# UI.net
KiCad netlist of a schematic drawn in Altium Designer
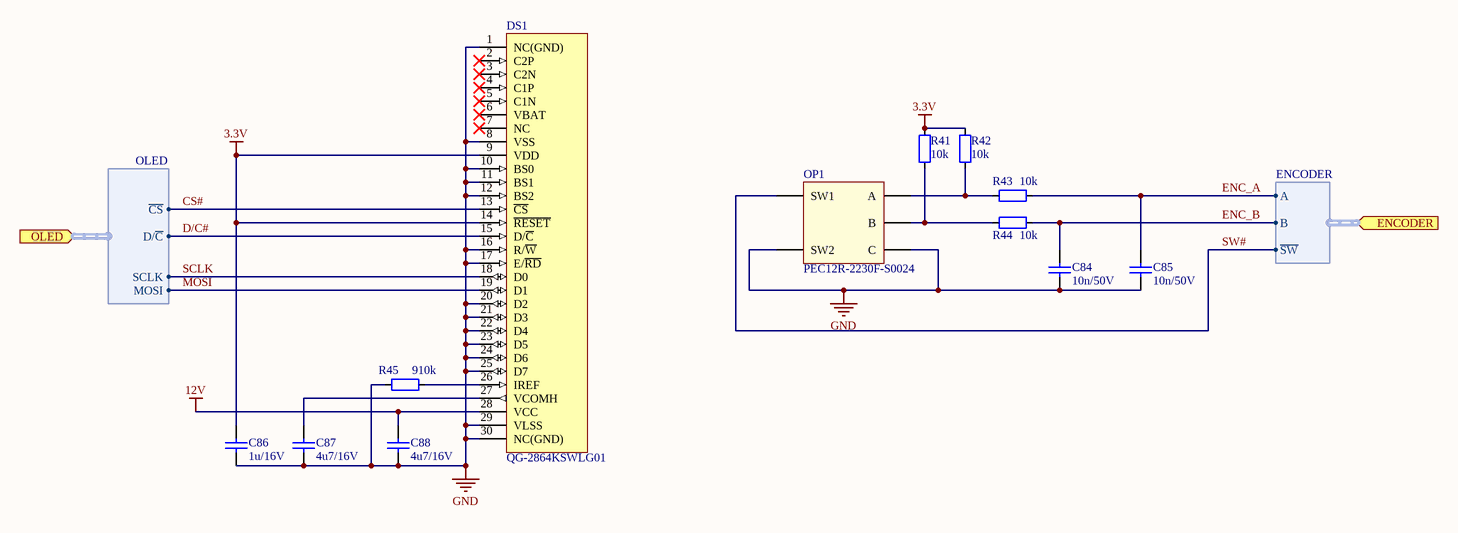
[diagram p0: UI.SchDoc]

(export (version "E")
  (design (tool "Eeschema 10.0.6"))
  (components
    (comp (ref "C84")
      (value "10n/50V")
      (footprint "C0402")
      (fields (field (name "VOLTAGE") "50V") (field (name "TOLERANCE") "10%"))
      (libsource (lib "dk_capacitors") (part "10n 50V X7R 0402"))
    )
    (comp (ref "C85")
      (value "10n/50V")
      (footprint "C0402")
      (fields (field (name "VOLTAGE") "50V") (field (name "TOLERANCE") "10%"))
      (libsource (lib "dk_capacitors") (part "10n 50V X7R 0402"))
    )
    (comp (ref "C86")
      (value "1u/16V")
      (footprint "C0603")
      (fields (field (name "VOLTAGE") "16V") (field (name "TOLERANCE") "10%"))
      (libsource (lib "dk_capacitors") (part "1u 16V X7R 0603"))
    )
    (comp (ref "C87")
      (value "4u7/16V")
      (footprint "C0805")
      (fields (field (name "VOLTAGE") "16V") (field (name "TOLERANCE") "10%"))
      (libsource (lib "dk_capacitors") (part "4u7 16V X7R 0805"))
    )
    (comp (ref "C88")
      (value "4u7/16V")
      (footprint "C0805")
      (fields (field (name "VOLTAGE") "16V") (field (name "TOLERANCE") "10%"))
      (libsource (lib "dk_capacitors") (part "4u7 16V X7R 0805"))
    )
    (comp (ref "DS1")
      (value "QG-2864KSWLG01")
      (footprint "QG-2864KSWLG01")
      (description "OLED, 1.3-inch, 128x64, SPI")
      (libsource (lib "dk_optoelectronics") (part "QG-2864KSWLG01"))
    )
    (comp (ref "OP1")
      (value "PEC12R-2230F-S0024")
      (footprint "PEC12R-2x30F-Sxxxx")
      (description "Rotary Encoder Mechanical 24 Quadrature (Incremental) Right Angle")
      (libsource (lib "dk_electromechanical") (part "PEC12R-2230F-S0024"))
    )
    (comp (ref "R41")
      (value "10k")
      (footprint "R0402")
      (fields (field (name "TOLERANCE") "1%") (field (name "VOLTAGE") "50V"))
      (libsource (lib "") (part "10k 63mW 50V 0402_1"))
    )
    (comp (ref "R42")
      (value "10k")
      (footprint "R0402")
      (fields (field (name "TOLERANCE") "1%") (field (name "VOLTAGE") "50V"))
      (libsource (lib "") (part "10k 63mW 50V 0402_1"))
    )
    (comp (ref "R43")
      (value "10k")
      (footprint "R0402")
      (fields (field (name "TOLERANCE") "1%") (field (name "VOLTAGE") "50V"))
      (libsource (lib "dk_resistors") (part "10k 63mW 50V 0402"))
    )
    (comp (ref "R44")
      (value "10k")
      (footprint "R0402")
      (fields (field (name "TOLERANCE") "1%") (field (name "VOLTAGE") "50V"))
      (libsource (lib "dk_resistors") (part "10k 63mW 50V 0402"))
    )
    (comp (ref "R45")
      (value "910k")
      (footprint "R0402")
      (fields (field (name "TOLERANCE") "5%") (field (name "VOLTAGE") "50V"))
      (libsource (lib "dk_resistors") (part "910k 63mW 50V 0402"))
    )
  )
  (nets
    (net (code "3") (name "/CS#") (class "Default")
      (node (ref "DS1") (pin "13") (pinfunction "~{CS}_13") (pintype "input"))
    )
    (net (code "4") (name "/D{slash}C#") (class "Default")
      (node (ref "DS1") (pin "15") (pinfunction "D/~{C}_15") (pintype "input"))
    )
    (net (code "5") (name "/ENC_A") (class "Default")
      (node (ref "C85") (pin "2") (pinfunction "2_2") (pintype "passive"))
      (node (ref "R43") (pin "2") (pinfunction "2_2") (pintype "passive"))
    )
    (net (code "6") (name "/ENC_B") (class "Default")
      (node (ref "C84") (pin "2") (pinfunction "2_2") (pintype "passive"))
      (node (ref "R44") (pin "2") (pinfunction "2_2") (pintype "passive"))
    )
    (net (code "7") (name "/MOSI") (class "Default")
      (node (ref "DS1") (pin "19") (pinfunction "D1_19") (pintype "bidirectional"))
    )
    (net (code "8") (name "/SCLK") (class "Default")
      (node (ref "DS1") (pin "18") (pinfunction "D0_18") (pintype "bidirectional"))
    )
    (net (code "9") (name "/SW#") (class "Default")
      (node (ref "OP1") (pin "1") (pinfunction "SW1_1") (pintype "passive"))
    )
    (net (code "12") (name "3.3V") (class "Default")
      (node (ref "C86") (pin "2") (pinfunction "2_2") (pintype "passive"))
      (node (ref "DS1") (pin "14") (pinfunction "~{RESET}_14") (pintype "input"))
      (node (ref "DS1") (pin "9") (pinfunction "VDD_9") (pintype "power_in"))
      (node (ref "R41") (pin "2") (pinfunction "2_2") (pintype "passive"))
      (node (ref "R42") (pin "2") (pinfunction "2_2") (pintype "passive"))
    )
    (net (code "13") (name "12V") (class "Default")
      (node (ref "C88") (pin "2") (pinfunction "2_2") (pintype "passive"))
      (node (ref "DS1") (pin "28") (pinfunction "VCC_28") (pintype "power_in"))
    )
    (net (code "14") (name "GND") (class "Default")
      (node (ref "C84") (pin "1") (pinfunction "1_1") (pintype "passive"))
      (node (ref "C85") (pin "1") (pinfunction "1_1") (pintype "passive"))
      (node (ref "C86") (pin "1") (pinfunction "1_1") (pintype "passive"))
      (node (ref "C87") (pin "1") (pinfunction "1_1") (pintype "passive"))
      (node (ref "C88") (pin "1") (pinfunction "1_1") (pintype "passive"))
      (node (ref "DS1") (pin "1") (pinfunction "NC(GND)_1") (pintype "passive"))
      (node (ref "DS1") (pin "10") (pinfunction "BS0_10") (pintype "input"))
      (node (ref "DS1") (pin "11") (pinfunction "BS1_11") (pintype "input"))
      (node (ref "DS1") (pin "12") (pinfunction "BS2_12") (pintype "input"))
      (node (ref "DS1") (pin "16") (pinfunction "R/~{W}_16") (pintype "input"))
      (node (ref "DS1") (pin "17") (pinfunction "E/~{RD}_17") (pintype "input"))
      (node (ref "DS1") (pin "20") (pinfunction "D2_20") (pintype "bidirectional"))
      (node (ref "DS1") (pin "21") (pinfunction "D3_21") (pintype "bidirectional"))
      (node (ref "DS1") (pin "22") (pinfunction "D4_22") (pintype "bidirectional"))
      (node (ref "DS1") (pin "23") (pinfunction "D5_23") (pintype "bidirectional"))
      (node (ref "DS1") (pin "24") (pinfunction "D6_24") (pintype "bidirectional"))
      (node (ref "DS1") (pin "25") (pinfunction "D7_25") (pintype "bidirectional"))
      (node (ref "DS1") (pin "29") (pinfunction "VLSS_29") (pintype "power_in"))
      (node (ref "DS1") (pin "30") (pinfunction "NC(GND)_30") (pintype "passive"))
      (node (ref "DS1") (pin "8") (pinfunction "VSS_8") (pintype "power_in"))
      (node (ref "OP1") (pin "2") (pinfunction "SW2_2") (pintype "passive"))
      (node (ref "OP1") (pin "C") (pinfunction "C_C") (pintype "passive"))
      (node (ref "R45") (pin "1") (pinfunction "1_1") (pintype "passive"))
    )
    (net (code "15") (name "Net-(DS1-IREF)") (class "Default")
      (node (ref "DS1") (pin "26") (pinfunction "IREF_26") (pintype "input"))
      (node (ref "R45") (pin "2") (pinfunction "2_2") (pintype "passive"))
    )
    (net (code "16") (name "Net-(DS1-VCOMH)") (class "Default")
      (node (ref "C87") (pin "2") (pinfunction "2_2") (pintype "passive"))
      (node (ref "DS1") (pin "27") (pinfunction "VCOMH_27") (pintype "output"))
    )
    (net (code "17") (name "Net-(OP1-PadA)") (class "Default")
      (node (ref "OP1") (pin "A") (pinfunction "A_A") (pintype "passive"))
      (node (ref "R42") (pin "1") (pinfunction "1_1") (pintype "passive"))
      (node (ref "R43") (pin "1") (pinfunction "1_1") (pintype "passive"))
    )
    (net (code "18") (name "Net-(OP1-PadB)") (class "Default")
      (node (ref "OP1") (pin "B") (pinfunction "B_B") (pintype "passive"))
      (node (ref "R41") (pin "1") (pinfunction "1_1") (pintype "passive"))
      (node (ref "R44") (pin "1") (pinfunction "1_1") (pintype "passive"))
    )
    (net (code "19") (name "unconnected-(DS1-C1N-Pad5)") (class "Default")
      (node (ref "DS1") (pin "5") (pinfunction "C1N_5") (pintype "input+no_connect"))
    )
    (net (code "20") (name "unconnected-(DS1-C1P-Pad4)") (class "Default")
      (node (ref "DS1") (pin "4") (pinfunction "C1P_4") (pintype "input+no_connect"))
    )
    (net (code "21") (name "unconnected-(DS1-C2N-Pad3)") (class "Default")
      (node (ref "DS1") (pin "3") (pinfunction "C2N_3") (pintype "input+no_connect"))
    )
    (net (code "22") (name "unconnected-(DS1-C2P-Pad2)") (class "Default")
      (node (ref "DS1") (pin "2") (pinfunction "C2P_2") (pintype "input+no_connect"))
    )
    (net (code "23") (name "unconnected-(DS1-NC-Pad7)") (class "Default")
      (node (ref "DS1") (pin "7") (pinfunction "NC_7") (pintype "passive+no_connect"))
    )
    (net (code "24") (name "unconnected-(DS1-VBAT-Pad6)") (class "Default")
      (node (ref "DS1") (pin "6") (pinfunction "VBAT_6") (pintype "power_in+no_connect"))
    )
  )
)
